# Charger.net
KiCad netlist of a schematic drawn in Altium Designer
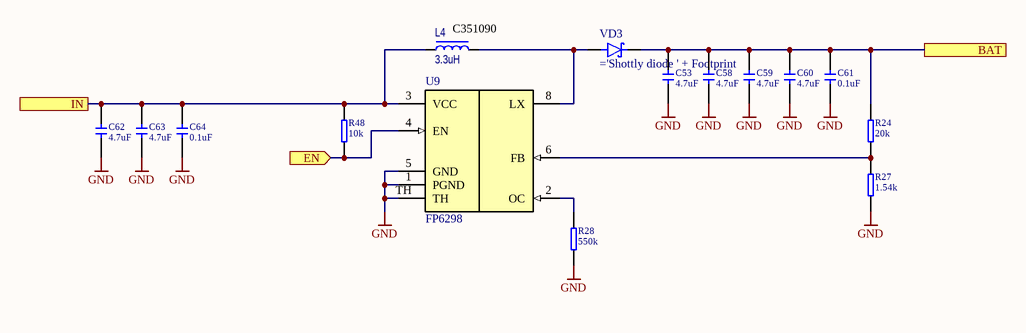
[diagram p0: Charger.SchDoc]

(export (version "E")
  (design (tool "Eeschema 10.0.6"))
  (components
    (comp (ref "C53")
      (value "4.7uF")
      (footprint "CERCAP 0603")
      (description "Capacitor")
      (fields (field (name "VOLTAGE") "16V") (field (name "Comment") "CERCAP 0603 4.7uF 16V X7R"))
      (libsource (lib "!main") (part "!Capacitor"))
    )
    (comp (ref "C58")
      (value "4.7uF")
      (footprint "CERCAP 0603")
      (description "Capacitor")
      (fields (field (name "VOLTAGE") "16V") (field (name "Comment") "CERCAP 0603 4.7uF 16V X7R"))
      (libsource (lib "!main") (part "!Capacitor"))
    )
    (comp (ref "C59")
      (value "4.7uF")
      (footprint "CERCAP 0603")
      (description "Capacitor")
      (fields (field (name "VOLTAGE") "16V") (field (name "Comment") "CERCAP 0603 4.7uF 16V X7R"))
      (libsource (lib "!main") (part "!Capacitor"))
    )
    (comp (ref "C60")
      (value "4.7uF")
      (footprint "CERCAP 0603")
      (description "Capacitor")
      (fields (field (name "VOLTAGE") "16V") (field (name "Comment") "CERCAP 0603 4.7uF 16V X7R"))
      (libsource (lib "!main") (part "!Capacitor"))
    )
    (comp (ref "C61")
      (value "0.1uF")
      (footprint "CERCAP 0402")
      (description "Capacitor")
      (fields (field (name "VOLTAGE") "50V") (field (name "Comment") "CERCAP 0402 0.1uF 50V X7R"))
      (libsource (lib "!main") (part "!Capacitor"))
    )
    (comp (ref "C62")
      (value "4.7uF")
      (footprint "CERCAP 0603")
      (description "Capacitor")
      (fields (field (name "VOLTAGE") "10V") (field (name "Comment") "CERCAP 0603 4.7uF 10V X7R"))
      (libsource (lib "!main") (part "!Capacitor"))
    )
    (comp (ref "C63")
      (value "4.7uF")
      (footprint "CERCAP 0603")
      (description "Capacitor")
      (fields (field (name "VOLTAGE") "10V") (field (name "Comment") "CERCAP 0603 4.7uF 10V X7R"))
      (libsource (lib "!main") (part "!Capacitor"))
    )
    (comp (ref "C64")
      (value "0.1uF")
      (footprint "CERCAP 0402")
      (description "Capacitor")
      (fields (field (name "VOLTAGE") "50V") (field (name "Comment") "CERCAP 0402 0.1uF 50V X7R"))
      (libsource (lib "!main") (part "!Capacitor"))
    )
    (comp (ref "L4")
      (value "3.3uH")
      (footprint "IND-4.6x4.6")
      (description "Inductor")
      (fields (field (name "Comment") "IND-4.6x4.6 3.3uH"))
      (libsource (lib "!main") (part "Inductor"))
    )
    (comp (ref "R24")
      (value "20k")
      (footprint "RES 0402")
      (description "Resistor")
      (fields (field (name "Comment") "RES 0402 20k"))
      (libsource (lib "!main") (part "!Resistor"))
    )
    (comp (ref "R27")
      (value "1.54k")
      (footprint "RES 0402")
      (description "Resistor")
      (fields (field (name "Comment") "RES 0402 1.54k"))
      (libsource (lib "!main") (part "!Resistor"))
    )
    (comp (ref "R28")
      (value "550k")
      (footprint "RES 0402")
      (description "Resistor")
      (fields (field (name "Comment") "RES 0402 550k"))
      (libsource (lib "!main") (part "!Resistor"))
    )
    (comp (ref "R48")
      (value "10k")
      (footprint "RES 0402")
      (description "Resistor")
      (fields (field (name "Comment") "RES 0402 10k"))
      (libsource (lib "!main") (part "!Resistor"))
    )
    (comp (ref "U9")
      (value "FP6298")
      (footprint "SO-8(EP)")
      (description "boost not-synq wEN woPG wCL")
      (libsource (lib "dc-dc") (part "FP6298"))
    )
    (comp (ref "VD3")
      (value "Shottly diode SOD-123")
      (footprint "SOD-123")
      (description "Diode Shottky")
      (libsource (lib "diodes") (part "DiodeS"))
    )
  )
  (nets
    (net (code "1") (name "/BAT") (class "Default")
      (node (ref "C53") (pin "2") (pintype "passive"))
      (node (ref "C58") (pin "2") (pintype "passive"))
      (node (ref "C59") (pin "2") (pintype "passive"))
      (node (ref "C60") (pin "2") (pintype "passive"))
      (node (ref "C61") (pin "2") (pintype "passive"))
      (node (ref "R24") (pin "2") (pinfunction "12_2") (pintype "passive"))
      (node (ref "VD3") (pin "C") (pinfunction "Cathode_C") (pintype "passive"))
    )
    (net (code "2") (name "/EN") (class "Default")
      (node (ref "R48") (pin "1") (pinfunction "11_1") (pintype "passive"))
      (node (ref "U9") (pin "4") (pinfunction "EN_4") (pintype "input"))
    )
    (net (code "3") (name "/IN") (class "Default")
      (node (ref "C62") (pin "2") (pintype "passive"))
      (node (ref "C63") (pin "2") (pintype "passive"))
      (node (ref "C64") (pin "2") (pintype "passive"))
      (node (ref "L4") (pin "1") (pinfunction "7_1") (pintype "passive"))
      (node (ref "R48") (pin "2") (pinfunction "12_2") (pintype "passive"))
      (node (ref "U9") (pin "3") (pinfunction "VCC_3") (pintype "power_in"))
    )
    (net (code "4") (name "GND") (class "Default")
      (node (ref "C53") (pin "1") (pintype "passive"))
      (node (ref "C58") (pin "1") (pintype "passive"))
      (node (ref "C59") (pin "1") (pintype "passive"))
      (node (ref "C60") (pin "1") (pintype "passive"))
      (node (ref "C61") (pin "1") (pintype "passive"))
      (node (ref "C62") (pin "1") (pintype "passive"))
      (node (ref "C63") (pin "1") (pintype "passive"))
      (node (ref "C64") (pin "1") (pintype "passive"))
      (node (ref "R27") (pin "1") (pinfunction "11_1") (pintype "passive"))
      (node (ref "R28") (pin "1") (pinfunction "11_1") (pintype "passive"))
      (node (ref "U9") (pin "1") (pinfunction "PGND_1") (pintype "power_in"))
      (node (ref "U9") (pin "5") (pinfunction "GND_5") (pintype "power_in"))
      (node (ref "U9") (pin "TH") (pinfunction "TH_TH") (pintype "power_in"))
    )
    (net (code "5") (name "Net-(L4-8)") (class "Default")
      (node (ref "L4") (pin "2") (pinfunction "8_2") (pintype "passive"))
      (node (ref "U9") (pin "8") (pinfunction "LX_8") (pintype "power_in"))
      (node (ref "VD3") (pin "A") (pinfunction "Anode_A") (pintype "passive"))
    )
    (net (code "6") (name "Net-(R24-11)") (class "Default")
      (node (ref "R24") (pin "1") (pinfunction "11_1") (pintype "passive"))
      (node (ref "R27") (pin "2") (pinfunction "12_2") (pintype "passive"))
      (node (ref "U9") (pin "6") (pinfunction "FB_6") (pintype "input"))
    )
    (net (code "7") (name "Net-(R28-12)") (class "Default")
      (node (ref "R28") (pin "2") (pinfunction "12_2") (pintype "passive"))
      (node (ref "U9") (pin "2") (pinfunction "OC_2") (pintype "input"))
    )
  )
)
